# indoor_servo_module.net
KiCad netlist of a schematic drawn in EAGLE
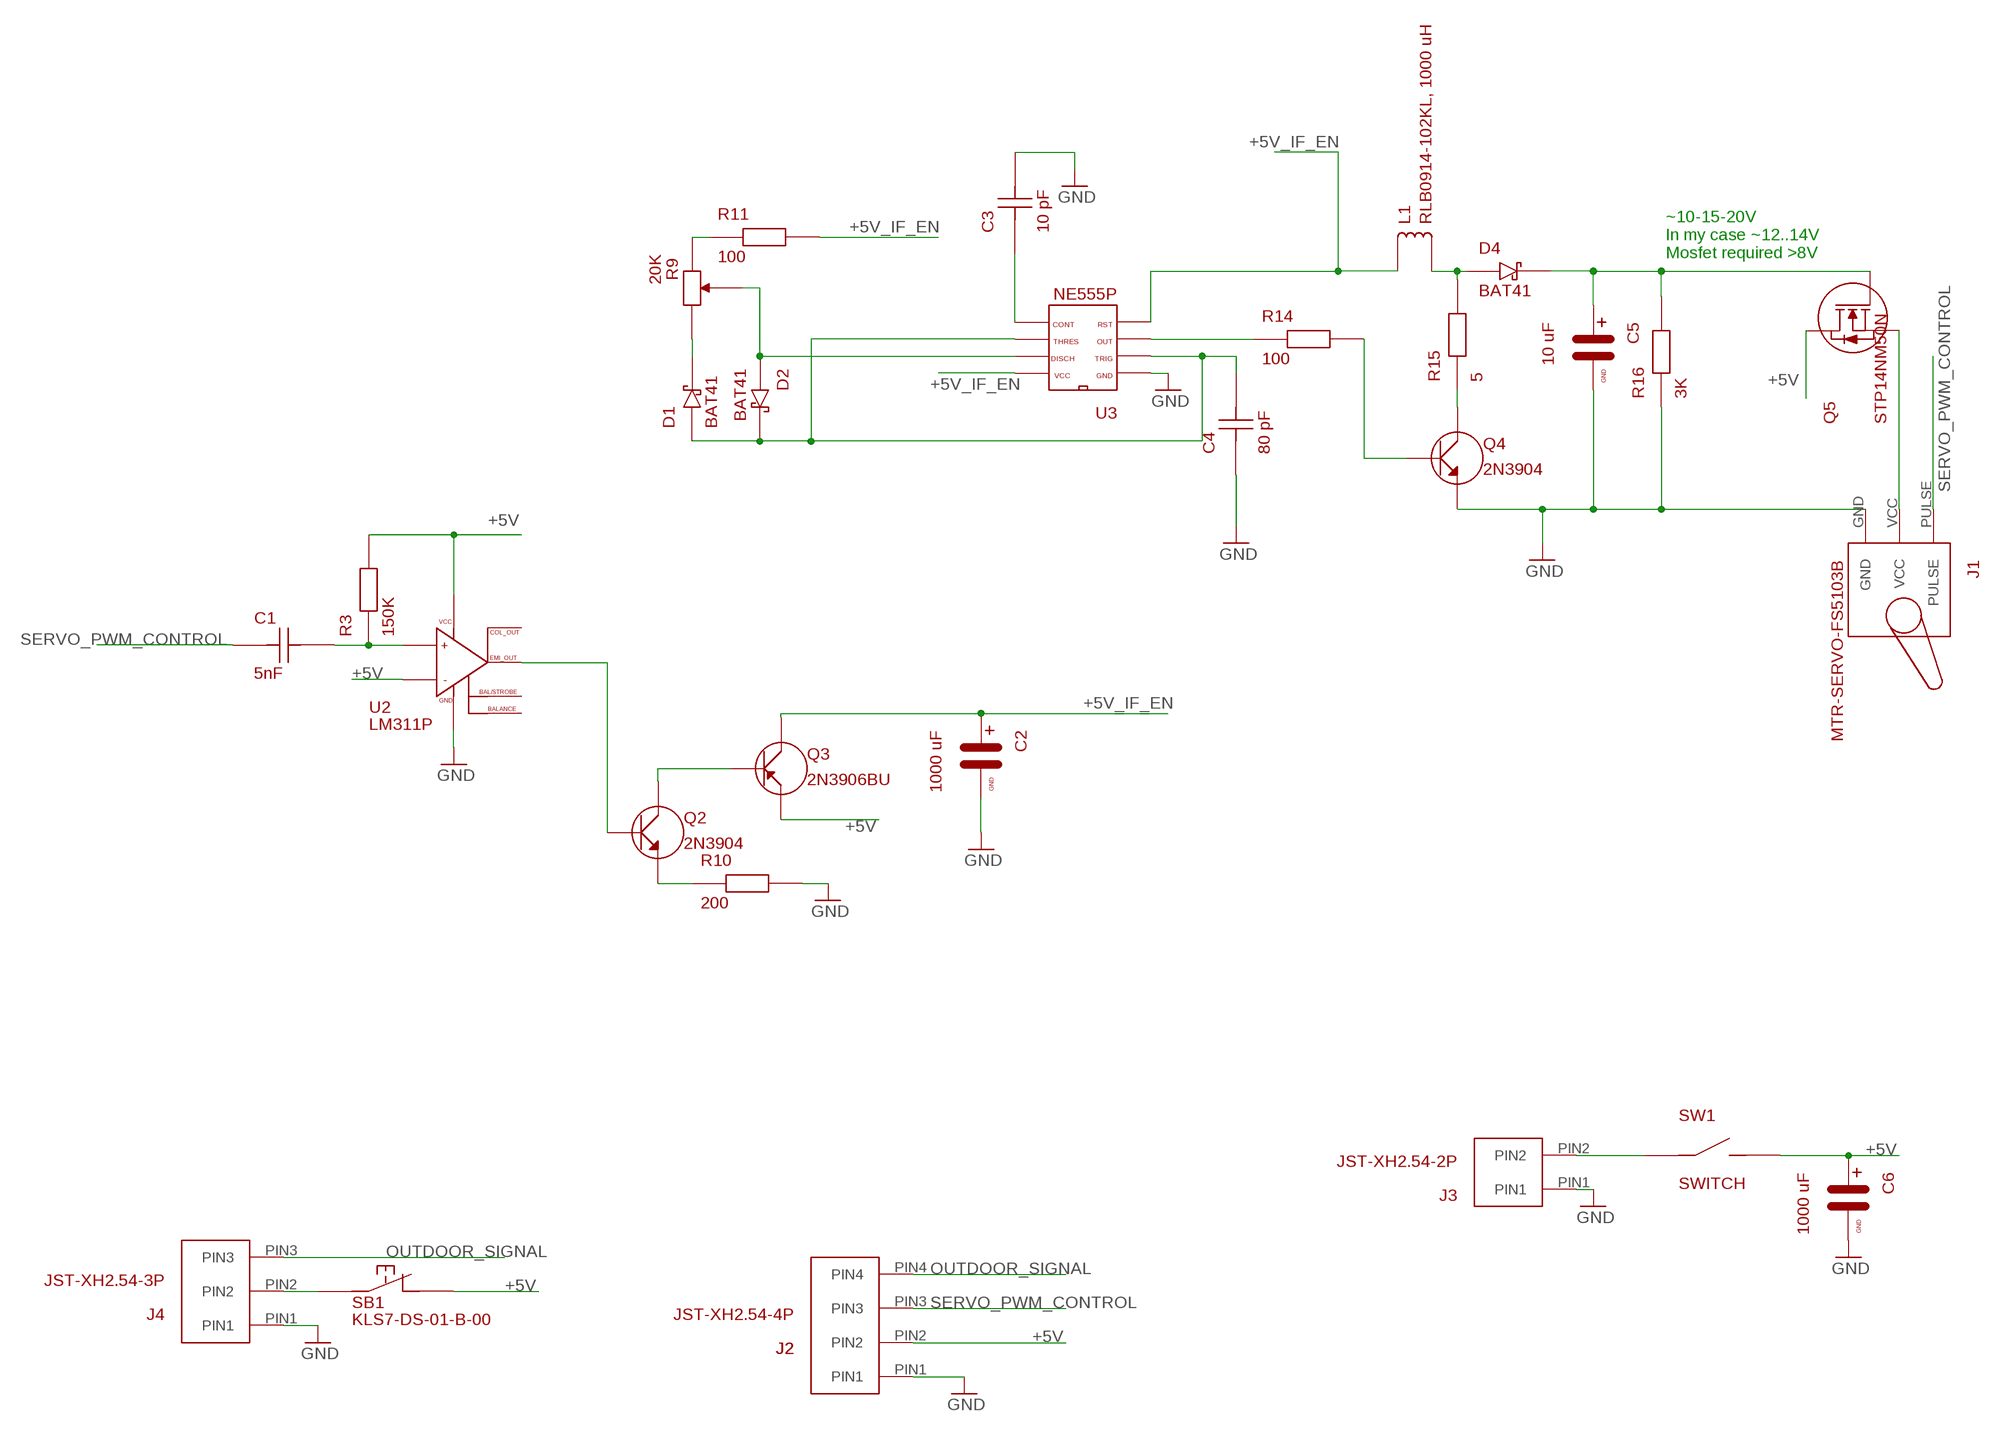
[diagram p0: schematic, sheet 1]

(export (version "E")
  (design (tool "Eeschema 10.0.6"))
  (components
    (comp (ref "C1")
      (value "5nF")
      (footprint "eagle-import:C-1")
      (libsource (lib "eagle-import") (part "C-1"))
    )
    (comp (ref "C2")
      (value "1000 uF")
      (footprint "eagle-import:C")
      (libsource (lib "eagle-import") (part "C"))
    )
    (comp (ref "C3")
      (value "10 pF")
      (footprint "eagle-import:C-1")
      (libsource (lib "eagle-import") (part "C-1"))
    )
    (comp (ref "C4")
      (value "80 pF")
      (footprint "eagle-import:C-1")
      (libsource (lib "eagle-import") (part "C-1"))
    )
    (comp (ref "C5") (value "10 uF") (footprint "eagle-import:C") (libsource (lib "eagle-import") (part "C")))
    (comp (ref "C6")
      (value "1000 uF")
      (footprint "eagle-import:C")
      (libsource (lib "eagle-import") (part "C"))
    )
    (comp (ref "D1")
      (value "BAT41")
      (footprint "eagle-import:D_SCHOTTKY")
      (libsource (lib "eagle-import") (part "D_SCHOTTKY"))
    )
    (comp (ref "D2")
      (value "BAT41")
      (footprint "eagle-import:D_SCHOTTKY")
      (libsource (lib "eagle-import") (part "D_SCHOTTKY"))
    )
    (comp (ref "D4")
      (value "BAT41")
      (footprint "eagle-import:D_SCHOTTKY")
      (libsource (lib "eagle-import") (part "D_SCHOTTKY"))
    )
    (comp (ref "J1")
      (value "MTR-SERVO-FS5103B")
      (footprint "eagle-import:SERVO")
      (libsource (lib "eagle-import") (part "SERVO"))
    )
    (comp (ref "J2")
      (value "JST-XH2.54-4P")
      (footprint "eagle-import:JST-XH254-4P")
      (libsource (lib "eagle-import") (part "JST-XH254-4P"))
    )
    (comp (ref "J3")
      (value "JST-XH2.54-2P")
      (footprint "eagle-import:JST-XH254-2P")
      (libsource (lib "eagle-import") (part "JST-XH254-2P"))
    )
    (comp (ref "J4")
      (value "JST-XH2.54-3P")
      (footprint "eagle-import:JST-XH254-3P")
      (libsource (lib "eagle-import") (part "JST-XH254-3P"))
    )
    (comp (ref "L1")
      (value "RLB0914-102KL, 1000 uH")
      (footprint "eagle-import:L-RLB0914")
      (libsource (lib "eagle-import") (part "L"))
    )
    (comp (ref "Q2")
      (value "2N3904")
      (footprint "eagle-import:TRANSISTOR")
      (libsource (lib "eagle-import") (part "TRANSISTOR_NPN"))
    )
    (comp (ref "Q3")
      (value "2N3906BU")
      (footprint "eagle-import:TRANSISTOR")
      (libsource (lib "eagle-import") (part "TRANSISTOR_PNP"))
    )
    (comp (ref "Q4")
      (value "2N3904")
      (footprint "eagle-import:TRANSISTOR")
      (libsource (lib "eagle-import") (part "TRANSISTOR_NPN"))
    )
    (comp (ref "Q5")
      (value "STP14NM50N")
      (footprint "eagle-import:MOSFET_N")
      (libsource (lib "eagle-import") (part "MOSFET_N"))
    )
    (comp (ref "R3") (value "150K") (footprint "eagle-import:R") (libsource (lib "eagle-import") (part "R")))
    (comp (ref "R9")
      (value "20K")
      (footprint "eagle-import:RD-3362H")
      (libsource (lib "eagle-import") (part "RD"))
    )
    (comp (ref "R10") (value "200") (footprint "eagle-import:R") (libsource (lib "eagle-import") (part "R")))
    (comp (ref "R11") (value "100") (footprint "eagle-import:R") (libsource (lib "eagle-import") (part "R")))
    (comp (ref "R14") (value "100") (footprint "eagle-import:R") (libsource (lib "eagle-import") (part "R")))
    (comp (ref "R15") (value "5") (footprint "eagle-import:R") (libsource (lib "eagle-import") (part "R")))
    (comp (ref "R16") (value "3K") (footprint "eagle-import:R") (libsource (lib "eagle-import") (part "R")))
    (comp (ref "SB1")
      (value "KLS7-DS-01-B-00")
      (footprint "eagle-import:SB-NC")
      (libsource (lib "eagle-import") (part "SB-NC"))
    )
    (comp (ref "SW1")
      (value "SWITCH")
      (footprint "eagle-import:SWITCH")
      (libsource (lib "eagle-import") (part "SWITCH"))
    )
    (comp (ref "U2")
      (value "LM311P")
      (footprint "eagle-import:DIP8")
      (libsource (lib "eagle-import") (part "LM311P"))
    )
    (comp (ref "U3")
      (value "NE555P")
      (footprint "eagle-import:DIP8")
      (libsource (lib "eagle-import") (part "NE555P"))
    )
  )
  (nets
    (net (code "1") (name "/+5V") (class "Default")
      (node (ref "C6") (pin "PIN_PLUS") (pinfunction "PIN_PLUS_PIN_PLUS") (pintype "bidirectional"))
      (node (ref "J2") (pin "PIN2") (pinfunction "PIN2_PIN2") (pintype "bidirectional"))
      (node (ref "Q3") (pin "E") (pinfunction "E_E") (pintype "bidirectional"))
      (node (ref "Q5") (pin "D") (pinfunction "D_D") (pintype "bidirectional"))
      (node (ref "R3") (pin "P$2") (pinfunction "P$2_P$2") (pintype "bidirectional"))
      (node (ref "SB1") (pin "P$2") (pinfunction "P$2_P$2") (pintype "bidirectional"))
      (node (ref "SW1") (pin "P$2") (pinfunction "P$2_P$2") (pintype "bidirectional"))
      (node (ref "U2") (pin "PIN_3") (pinfunction "IN-_PIN_3") (pintype "input"))
      (node (ref "U2") (pin "PIN_8") (pinfunction "VCC_PIN_8") (pintype "power_in"))
    )
    (net (code "2") (name "/+5V_IF_EN") (class "Default")
      (node (ref "C2") (pin "PIN_PLUS") (pinfunction "PIN_PLUS_PIN_PLUS") (pintype "bidirectional"))
      (node (ref "L1") (pin "P$1") (pinfunction "P$1_P$1") (pintype "bidirectional"))
      (node (ref "Q3") (pin "C") (pinfunction "C_C") (pintype "bidirectional"))
      (node (ref "R11") (pin "P$2") (pinfunction "P$2_P$2") (pintype "bidirectional"))
      (node (ref "U3") (pin "PIN_4") (pinfunction "RESET_PIN_4") (pintype "bidirectional"))
      (node (ref "U3") (pin "PIN_8") (pinfunction "VCC_PIN_8") (pintype "power_in"))
    )
    (net (code "3") (name "/OUTDOOR_SIGNAL") (class "Default")
      (node (ref "J2") (pin "PIN4") (pinfunction "PIN4_PIN4") (pintype "bidirectional"))
      (node (ref "J4") (pin "PIN3") (pinfunction "PIN3_PIN3") (pintype "bidirectional"))
    )
    (net (code "4") (name "/SERVO_PWM_CONTROL") (class "Default")
      (node (ref "C1") (pin "P$1") (pinfunction "P$1_P$1") (pintype "bidirectional"))
      (node (ref "J1") (pin "PULSE") (pinfunction "PULSE_PULSE") (pintype "input"))
      (node (ref "J2") (pin "PIN3") (pinfunction "PIN3_PIN3") (pintype "bidirectional"))
    )
    (net (code "5") (name "GND") (class "Default")
      (node (ref "C2") (pin "PIN_GND") (pinfunction "PIN_GND_PIN_GND") (pintype "bidirectional"))
      (node (ref "C3") (pin "P$2") (pinfunction "P$2_P$2") (pintype "bidirectional"))
      (node (ref "C4") (pin "P$1") (pinfunction "P$1_P$1") (pintype "bidirectional"))
      (node (ref "C5") (pin "PIN_GND") (pinfunction "PIN_GND_PIN_GND") (pintype "bidirectional"))
      (node (ref "C6") (pin "PIN_GND") (pinfunction "PIN_GND_PIN_GND") (pintype "bidirectional"))
      (node (ref "J1") (pin "GND") (pinfunction "GND_GND") (pintype "power_in"))
      (node (ref "J2") (pin "PIN1") (pinfunction "PIN1_PIN1") (pintype "bidirectional"))
      (node (ref "J3") (pin "PIN1") (pinfunction "PIN1_PIN1") (pintype "bidirectional"))
      (node (ref "J4") (pin "PIN1") (pinfunction "PIN1_PIN1") (pintype "bidirectional"))
      (node (ref "Q4") (pin "E") (pinfunction "E_E") (pintype "bidirectional"))
      (node (ref "R10") (pin "P$2") (pinfunction "P$2_P$2") (pintype "bidirectional"))
      (node (ref "R16") (pin "P$1") (pinfunction "P$1_P$1") (pintype "bidirectional"))
      (node (ref "U2") (pin "PIN_4") (pinfunction "GND_PIN_4") (pintype "power_in"))
      (node (ref "U3") (pin "PIN_1") (pinfunction "GND_PIN_1") (pintype "power_in"))
    )
    (net (code "6") (name "Net-(C5-PadPIN_PLUS)") (class "Default")
      (node (ref "C5") (pin "PIN_PLUS") (pinfunction "PIN_PLUS_PIN_PLUS") (pintype "bidirectional"))
      (node (ref "D4") (pin "CATHODE") (pinfunction "CATHODE_CATHODE") (pintype "bidirectional"))
      (node (ref "Q5") (pin "G") (pinfunction "G_G") (pintype "bidirectional"))
      (node (ref "R16") (pin "P$2") (pinfunction "P$2_P$2") (pintype "bidirectional"))
    )
    (net (code "7") (name "Net-(D1-PadCATHODE)") (class "Default")
      (node (ref "D1") (pin "CATHODE") (pinfunction "CATHODE_CATHODE") (pintype "bidirectional"))
      (node (ref "R9") (pin "P2") (pinfunction "P2_P2") (pintype "bidirectional"))
    )
    (net (code "8") (name "Net-(D4-PadANODE)") (class "Default")
      (node (ref "D4") (pin "ANODE") (pinfunction "ANODE_ANODE") (pintype "bidirectional"))
      (node (ref "L1") (pin "P$2") (pinfunction "P$2_P$2") (pintype "bidirectional"))
      (node (ref "R15") (pin "P$2") (pinfunction "P$2_P$2") (pintype "bidirectional"))
    )
    (net (code "9") (name "Net-(J1-PadVCC)") (class "Default")
      (node (ref "J1") (pin "VCC") (pinfunction "VCC_VCC") (pintype "power_in"))
      (node (ref "Q5") (pin "S") (pinfunction "S_S") (pintype "bidirectional"))
    )
    (net (code "10") (name "Net-(J3-PadPIN2)") (class "Default")
      (node (ref "J3") (pin "PIN2") (pinfunction "PIN2_PIN2") (pintype "bidirectional"))
      (node (ref "SW1") (pin "P$1") (pinfunction "P$1_P$1") (pintype "bidirectional"))
    )
    (net (code "11") (name "Net-(J4-PadPIN2)") (class "Default")
      (node (ref "J4") (pin "PIN2") (pinfunction "PIN2_PIN2") (pintype "bidirectional"))
      (node (ref "SB1") (pin "P$1") (pinfunction "P$1_P$1") (pintype "bidirectional"))
    )
    (net (code "12") (name "Net-(Q2-PadC)") (class "Default")
      (node (ref "Q2") (pin "C") (pinfunction "C_C") (pintype "bidirectional"))
      (node (ref "Q3") (pin "B") (pinfunction "B_B") (pintype "bidirectional"))
    )
    (net (code "13") (name "Net-(Q2-PadE)") (class "Default")
      (node (ref "Q2") (pin "E") (pinfunction "E_E") (pintype "bidirectional"))
      (node (ref "R10") (pin "P$1") (pinfunction "P$1_P$1") (pintype "bidirectional"))
    )
    (net (code "14") (name "Net-(Q4-PadB)") (class "Default")
      (node (ref "Q4") (pin "B") (pinfunction "B_B") (pintype "bidirectional"))
      (node (ref "R14") (pin "P$2") (pinfunction "P$2_P$2") (pintype "bidirectional"))
    )
    (net (code "15") (name "Net-(Q4-PadC)") (class "Default")
      (node (ref "Q4") (pin "C") (pinfunction "C_C") (pintype "bidirectional"))
      (node (ref "R15") (pin "P$1") (pinfunction "P$1_P$1") (pintype "bidirectional"))
    )
    (net (code "16") (name "Net-(R11-PadP$1)") (class "Default")
      (node (ref "R11") (pin "P$1") (pinfunction "P$1_P$1") (pintype "bidirectional"))
      (node (ref "R9") (pin "P1") (pinfunction "P1_P1") (pintype "bidirectional"))
    )
    (net (code "17") (name "Net-(U2-EMI_OUT)") (class "Default")
      (node (ref "Q2") (pin "B") (pinfunction "B_B") (pintype "bidirectional"))
      (node (ref "U2") (pin "PIN_1") (pinfunction "EMI_OUT_PIN_1") (pintype "output"))
    )
    (net (code "18") (name "Net-(U2-IN+)") (class "Default")
      (node (ref "C1") (pin "P$2") (pinfunction "P$2_P$2") (pintype "bidirectional"))
      (node (ref "R3") (pin "P$1") (pinfunction "P$1_P$1") (pintype "bidirectional"))
      (node (ref "U2") (pin "PIN_2") (pinfunction "IN+_PIN_2") (pintype "input"))
    )
    (net (code "19") (name "Net-(U3-CONT)") (class "Default")
      (node (ref "C3") (pin "P$1") (pinfunction "P$1_P$1") (pintype "bidirectional"))
      (node (ref "U3") (pin "PIN_5") (pinfunction "CONT_PIN_5") (pintype "bidirectional"))
    )
    (net (code "20") (name "Net-(U3-DISCH)") (class "Default")
      (node (ref "D2") (pin "ANODE") (pinfunction "ANODE_ANODE") (pintype "bidirectional"))
      (node (ref "R9") (pin "P3") (pinfunction "P3_P3") (pintype "bidirectional"))
      (node (ref "U3") (pin "PIN_7") (pinfunction "DISCH_PIN_7") (pintype "bidirectional"))
    )
    (net (code "21") (name "Net-(U3-OUT)") (class "Default")
      (node (ref "R14") (pin "P$1") (pinfunction "P$1_P$1") (pintype "bidirectional"))
      (node (ref "U3") (pin "PIN_3") (pinfunction "OUT_PIN_3") (pintype "output"))
    )
    (net (code "22") (name "Net-(U3-THRES)") (class "Default")
      (node (ref "C4") (pin "P$2") (pinfunction "P$2_P$2") (pintype "bidirectional"))
      (node (ref "D1") (pin "ANODE") (pinfunction "ANODE_ANODE") (pintype "bidirectional"))
      (node (ref "D2") (pin "CATHODE") (pinfunction "CATHODE_CATHODE") (pintype "bidirectional"))
      (node (ref "U3") (pin "PIN_2") (pinfunction "TRIG_PIN_2") (pintype "bidirectional"))
      (node (ref "U3") (pin "PIN_6") (pinfunction "THRES_PIN_6") (pintype "bidirectional"))
    )
    (net (code "23") (name "unconnected-(U2-BALANCE-PadPIN_5)") (class "Default")
      (node (ref "U2") (pin "PIN_5") (pinfunction "BALANCE_PIN_5") (pintype "input"))
    )
    (net (code "24") (name "unconnected-(U2-BAL_STROBE-PadPIN_6)") (class "Default")
      (node (ref "U2") (pin "PIN_6") (pinfunction "BAL_STROBE_PIN_6") (pintype "input"))
    )
    (net (code "25") (name "unconnected-(U2-COL_OUT-PadPIN_7)") (class "Default")
      (node (ref "U2") (pin "PIN_7") (pinfunction "COL_OUT_PIN_7") (pintype "output"))
    )
  )
)
